# motor-slaves.net
KiCad netlist of a schematic drawn in EAGLE
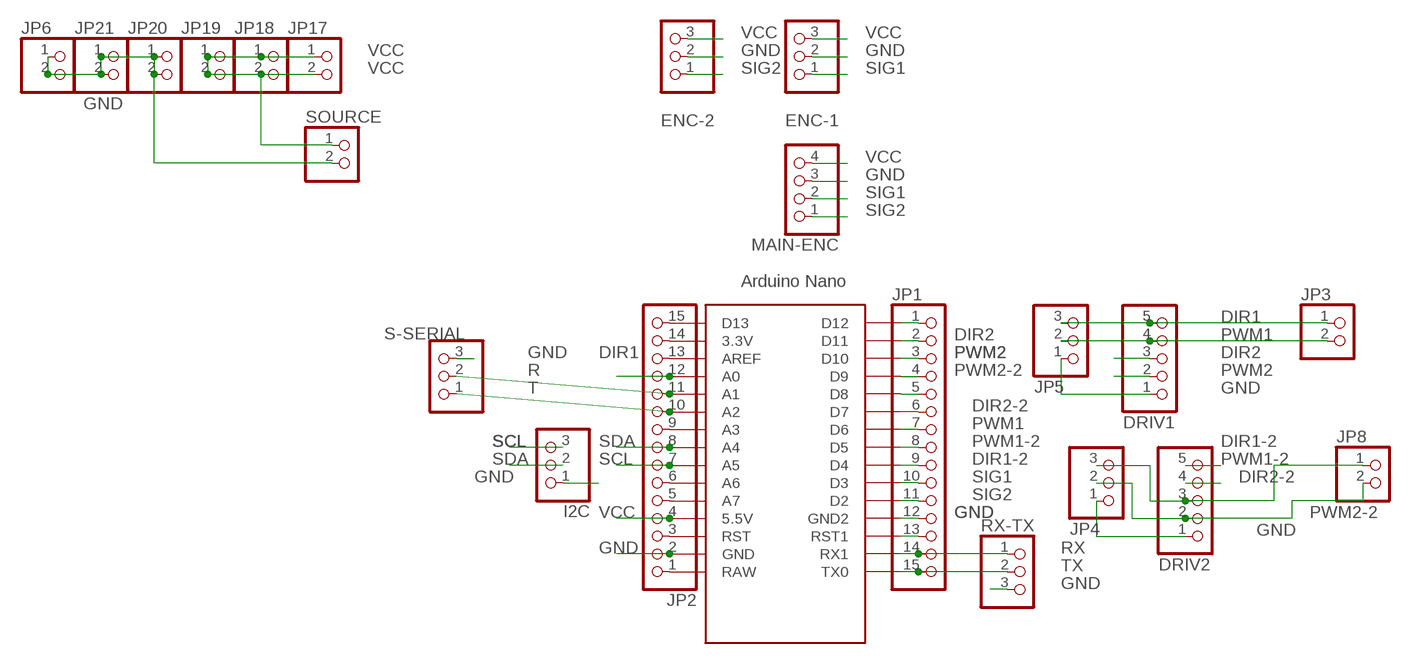
[diagram p0: schematic, sheet 1]

(export (version "E")
  (design (tool "Eeschema 10.0.6"))
  (components
    (comp (ref "DRIV1")
      (value "PINHD-5_DATA")
      (footprint "eagle-import:1X05_DATA")
      (libsource (lib "eagle-import") (part "PINHD-5_DATA"))
    )
    (comp (ref "DRIV2")
      (value "PINHD-5_DATA")
      (footprint "eagle-import:1X05_DATA")
      (libsource (lib "eagle-import") (part "PINHD-5_DATA"))
    )
    (comp (ref "ENC-1")
      (value "PINHD-3_DATA")
      (footprint "eagle-import:1X03_DATA")
      (libsource (lib "eagle-import") (part "PINHD-3_DATA"))
    )
    (comp (ref "ENC-2")
      (value "PINHD-3_DATA")
      (footprint "eagle-import:1X03_DATA")
      (libsource (lib "eagle-import") (part "PINHD-3_DATA"))
    )
    (comp (ref "I2C")
      (value "PINHD-3_DATA")
      (footprint "eagle-import:1X03_DATA")
      (libsource (lib "eagle-import") (part "PINHD-3_DATA"))
    )
    (comp (ref "JP1")
      (value "PINHD-1X15")
      (footprint "eagle-import:1X15")
      (libsource (lib "eagle-import") (part "PINHD-1X15"))
    )
    (comp (ref "JP2")
      (value "PINHD-1X15")
      (footprint "eagle-import:1X15")
      (libsource (lib "eagle-import") (part "PINHD-1X15"))
    )
    (comp (ref "JP3")
      (value "PINHD-2_DATA")
      (footprint "eagle-import:1X02_DATA")
      (libsource (lib "eagle-import") (part "PINHD-2_DATA"))
    )
    (comp (ref "JP4")
      (value "PINHD-3_DATA")
      (footprint "eagle-import:1X03_DATA")
      (libsource (lib "eagle-import") (part "PINHD-3_DATA"))
    )
    (comp (ref "JP5")
      (value "PINHD-3_DATA")
      (footprint "eagle-import:1X03_DATA")
      (libsource (lib "eagle-import") (part "PINHD-3_DATA"))
    )
    (comp (ref "JP6")
      (value "PINHD-1X2")
      (footprint "eagle-import:1X02")
      (libsource (lib "eagle-import") (part "PINHD-1X2"))
    )
    (comp (ref "JP8")
      (value "PINHD-2_DATA")
      (footprint "eagle-import:1X02_DATA")
      (libsource (lib "eagle-import") (part "PINHD-2_DATA"))
    )
    (comp (ref "JP17")
      (value "PINHD-1X2")
      (footprint "eagle-import:1X02")
      (libsource (lib "eagle-import") (part "PINHD-1X2"))
    )
    (comp (ref "JP18")
      (value "PINHD-1X2")
      (footprint "eagle-import:1X02")
      (libsource (lib "eagle-import") (part "PINHD-1X2"))
    )
    (comp (ref "JP19")
      (value "PINHD-1X2")
      (footprint "eagle-import:1X02")
      (libsource (lib "eagle-import") (part "PINHD-1X2"))
    )
    (comp (ref "JP20")
      (value "PINHD-1X2")
      (footprint "eagle-import:1X02")
      (libsource (lib "eagle-import") (part "PINHD-1X2"))
    )
    (comp (ref "JP21")
      (value "PINHD-1X2")
      (footprint "eagle-import:1X02")
      (libsource (lib "eagle-import") (part "PINHD-1X2"))
    )
    (comp (ref "MAIN-ENC")
      (value "PINHD-4_DATA")
      (footprint "eagle-import:1X04_DATA")
      (libsource (lib "eagle-import") (part "PINHD-4_DATA"))
    )
    (comp (ref "RX-TX")
      (value "PINHD-3_DATA")
      (footprint "eagle-import:1X03_DATA")
      (libsource (lib "eagle-import") (part "PINHD-3_DATA"))
    )
    (comp (ref "S-SERIAL")
      (value "PINHD-3_DATA")
      (footprint "eagle-import:1X03_DATA")
      (libsource (lib "eagle-import") (part "PINHD-3_DATA"))
    )
    (comp (ref "SOURCE")
      (value "PINHD-1X2")
      (footprint "eagle-import:1X02")
      (libsource (lib "eagle-import") (part "PINHD-1X2"))
    )
    (comp (ref "U$1")
      (value "ARDUINO_NANO")
      (footprint "eagle-import:NANO")
      (libsource (lib "eagle-import") (part "ARDUINO_NANO"))
    )
  )
  (nets
    (net (code "1") (name "/DIR1") (class "Default")
      (node (ref "DRIV1") (pin "5") (pinfunction "5_5") (pintype "passive"))
      (node (ref "JP2") (pin "12") (pinfunction "12_12") (pintype "passive"))
      (node (ref "JP3") (pin "1") (pinfunction "1_1") (pintype "passive"))
      (node (ref "JP5") (pin "3") (pinfunction "3_3") (pintype "passive"))
      (node (ref "U$1") (pin "A0") (pinfunction "A0_A0") (pintype "bidirectional"))
    )
    (net (code "2") (name "/DIR1-2") (class "Default")
      (node (ref "DRIV2") (pin "5") (pinfunction "5_5") (pintype "passive"))
      (node (ref "JP1") (pin "9") (pinfunction "9_9") (pintype "passive"))
      (node (ref "U$1") (pin "D4") (pinfunction "D4_D4") (pintype "bidirectional"))
    )
    (net (code "3") (name "/DIR2") (class "Default")
      (node (ref "DRIV1") (pin "3") (pinfunction "3_3") (pintype "passive"))
      (node (ref "JP1") (pin "2") (pinfunction "2_2") (pintype "passive"))
      (node (ref "U$1") (pin "D11") (pinfunction "D11_D11") (pintype "bidirectional"))
    )
    (net (code "4") (name "/DIR2-2") (class "Default")
      (node (ref "DRIV2") (pin "3") (pinfunction "3_3") (pintype "passive"))
      (node (ref "JP1") (pin "6") (pinfunction "6_6") (pintype "passive"))
      (node (ref "JP4") (pin "3") (pinfunction "3_3") (pintype "passive"))
      (node (ref "JP8") (pin "1") (pinfunction "1_1") (pintype "passive"))
      (node (ref "U$1") (pin "D7") (pinfunction "D7_D7") (pintype "bidirectional"))
    )
    (net (code "5") (name "/GND") (class "Default")
      (node (ref "DRIV1") (pin "1") (pinfunction "1_1") (pintype "passive"))
      (node (ref "DRIV2") (pin "1") (pinfunction "1_1") (pintype "passive"))
      (node (ref "ENC-1") (pin "2") (pinfunction "2_2") (pintype "passive"))
      (node (ref "ENC-2") (pin "2") (pinfunction "2_2") (pintype "passive"))
      (node (ref "I2C") (pin "1") (pinfunction "1_1") (pintype "passive"))
      (node (ref "JP1") (pin "12") (pinfunction "12_12") (pintype "passive"))
      (node (ref "JP2") (pin "2") (pinfunction "2_2") (pintype "passive"))
      (node (ref "JP20") (pin "1") (pinfunction "1_1") (pintype "passive"))
      (node (ref "JP20") (pin "2") (pinfunction "2_2") (pintype "passive"))
      (node (ref "JP21") (pin "1") (pinfunction "1_1") (pintype "passive"))
      (node (ref "JP21") (pin "2") (pinfunction "2_2") (pintype "passive"))
      (node (ref "JP4") (pin "1") (pinfunction "1_1") (pintype "passive"))
      (node (ref "JP5") (pin "1") (pinfunction "1_1") (pintype "passive"))
      (node (ref "JP6") (pin "1") (pinfunction "1_1") (pintype "passive"))
      (node (ref "JP6") (pin "2") (pinfunction "2_2") (pintype "passive"))
      (node (ref "MAIN-ENC") (pin "3") (pinfunction "3_3") (pintype "passive"))
      (node (ref "RX-TX") (pin "3") (pinfunction "3_3") (pintype "passive"))
      (node (ref "S-SERIAL") (pin "3") (pinfunction "3_3") (pintype "passive"))
      (node (ref "SOURCE") (pin "2") (pinfunction "2_2") (pintype "passive"))
      (node (ref "U$1") (pin "GND") (pinfunction "GND_GND") (pintype "bidirectional"))
      (node (ref "U$1") (pin "GND1") (pinfunction "GND2_GND1") (pintype "bidirectional"))
    )
    (net (code "6") (name "/PWM1") (class "Default")
      (node (ref "DRIV1") (pin "4") (pinfunction "4_4") (pintype "passive"))
      (node (ref "JP1") (pin "7") (pinfunction "7_7") (pintype "passive"))
      (node (ref "JP3") (pin "2") (pinfunction "2_2") (pintype "passive"))
      (node (ref "JP5") (pin "2") (pinfunction "2_2") (pintype "passive"))
      (node (ref "U$1") (pin "D6") (pinfunction "D6_D6") (pintype "bidirectional"))
    )
    (net (code "7") (name "/PWM1-2") (class "Default")
      (node (ref "DRIV2") (pin "4") (pinfunction "4_4") (pintype "passive"))
      (node (ref "JP1") (pin "8") (pinfunction "8_8") (pintype "passive"))
      (node (ref "U$1") (pin "D5") (pinfunction "D5_D5") (pintype "bidirectional"))
    )
    (net (code "8") (name "/PWM2") (class "Default")
      (node (ref "DRIV1") (pin "2") (pinfunction "2_2") (pintype "passive"))
      (node (ref "JP1") (pin "3") (pinfunction "3_3") (pintype "passive"))
      (node (ref "U$1") (pin "D10") (pinfunction "D10_D10") (pintype "bidirectional"))
    )
    (net (code "9") (name "/PWM2-2") (class "Default")
      (node (ref "DRIV2") (pin "2") (pinfunction "2_2") (pintype "passive"))
      (node (ref "JP1") (pin "4") (pinfunction "4_4") (pintype "passive"))
      (node (ref "JP4") (pin "2") (pinfunction "2_2") (pintype "passive"))
      (node (ref "JP8") (pin "2") (pinfunction "2_2") (pintype "passive"))
      (node (ref "U$1") (pin "D9") (pinfunction "D9_D9") (pintype "bidirectional"))
    )
    (net (code "10") (name "/R") (class "Default")
      (node (ref "JP2") (pin "11") (pinfunction "11_11") (pintype "passive"))
      (node (ref "S-SERIAL") (pin "2") (pinfunction "2_2") (pintype "passive"))
      (node (ref "U$1") (pin "A1") (pinfunction "A1_A1") (pintype "bidirectional"))
    )
    (net (code "11") (name "/RX") (class "Default")
      (node (ref "JP1") (pin "14") (pinfunction "14_14") (pintype "passive"))
      (node (ref "RX-TX") (pin "1") (pinfunction "1_1") (pintype "passive"))
      (node (ref "U$1") (pin "RX1") (pinfunction "RX1_RX1") (pintype "bidirectional"))
    )
    (net (code "12") (name "/SCL") (class "Default")
      (node (ref "I2C") (pin "3") (pinfunction "3_3") (pintype "passive"))
      (node (ref "JP2") (pin "7") (pinfunction "7_7") (pintype "passive"))
      (node (ref "U$1") (pin "A5") (pinfunction "A5_A5") (pintype "bidirectional"))
    )
    (net (code "13") (name "/SDA") (class "Default")
      (node (ref "I2C") (pin "2") (pinfunction "2_2") (pintype "passive"))
      (node (ref "JP2") (pin "8") (pinfunction "8_8") (pintype "passive"))
      (node (ref "U$1") (pin "A4") (pinfunction "A4_A4") (pintype "bidirectional"))
    )
    (net (code "14") (name "/SIG1") (class "Default")
      (node (ref "ENC-1") (pin "1") (pinfunction "1_1") (pintype "passive"))
      (node (ref "JP1") (pin "10") (pinfunction "10_10") (pintype "passive"))
      (node (ref "MAIN-ENC") (pin "2") (pinfunction "2_2") (pintype "passive"))
      (node (ref "U$1") (pin "D3") (pinfunction "D3_D3") (pintype "bidirectional"))
    )
    (net (code "15") (name "/SIG2") (class "Default")
      (node (ref "ENC-2") (pin "1") (pinfunction "1_1") (pintype "passive"))
      (node (ref "JP1") (pin "11") (pinfunction "11_11") (pintype "passive"))
      (node (ref "MAIN-ENC") (pin "1") (pinfunction "1_1") (pintype "passive"))
      (node (ref "U$1") (pin "D2") (pinfunction "D2_D2") (pintype "bidirectional"))
    )
    (net (code "16") (name "/T") (class "Default")
      (node (ref "JP2") (pin "10") (pinfunction "10_10") (pintype "passive"))
      (node (ref "S-SERIAL") (pin "1") (pinfunction "1_1") (pintype "passive"))
      (node (ref "U$1") (pin "A2") (pinfunction "A2_A2") (pintype "bidirectional"))
    )
    (net (code "17") (name "/TX") (class "Default")
      (node (ref "JP1") (pin "15") (pinfunction "15_15") (pintype "passive"))
      (node (ref "RX-TX") (pin "2") (pinfunction "2_2") (pintype "passive"))
      (node (ref "U$1") (pin "TX0") (pinfunction "TX0_TX0") (pintype "bidirectional"))
    )
    (net (code "18") (name "/VCC") (class "Default")
      (node (ref "ENC-1") (pin "3") (pinfunction "3_3") (pintype "passive"))
      (node (ref "ENC-2") (pin "3") (pinfunction "3_3") (pintype "passive"))
      (node (ref "JP17") (pin "1") (pinfunction "1_1") (pintype "passive"))
      (node (ref "JP17") (pin "2") (pinfunction "2_2") (pintype "passive"))
      (node (ref "JP18") (pin "1") (pinfunction "1_1") (pintype "passive"))
      (node (ref "JP18") (pin "2") (pinfunction "2_2") (pintype "passive"))
      (node (ref "JP19") (pin "1") (pinfunction "1_1") (pintype "passive"))
      (node (ref "JP19") (pin "2") (pinfunction "2_2") (pintype "passive"))
      (node (ref "JP2") (pin "4") (pinfunction "4_4") (pintype "passive"))
      (node (ref "MAIN-ENC") (pin "4") (pinfunction "4_4") (pintype "passive"))
      (node (ref "SOURCE") (pin "1") (pinfunction "1_1") (pintype "passive"))
      (node (ref "U$1") (pin "5V") (pinfunction "5.5V_5V") (pintype "bidirectional"))
    )
    (net (code "19") (name "Net-(JP1-Pad1)") (class "Default")
      (node (ref "JP1") (pin "1") (pinfunction "1_1") (pintype "passive"))
      (node (ref "U$1") (pin "D12") (pinfunction "D12_D12") (pintype "bidirectional"))
    )
    (net (code "20") (name "Net-(JP1-Pad5)") (class "Default")
      (node (ref "JP1") (pin "5") (pinfunction "5_5") (pintype "passive"))
      (node (ref "U$1") (pin "D8") (pinfunction "D8_D8") (pintype "bidirectional"))
    )
    (net (code "21") (name "Net-(JP1-Pad13)") (class "Default")
      (node (ref "JP1") (pin "13") (pinfunction "13_13") (pintype "passive"))
      (node (ref "U$1") (pin "RST1") (pinfunction "RST1_RST1") (pintype "bidirectional"))
    )
    (net (code "22") (name "Net-(JP2-Pad1)") (class "Default")
      (node (ref "JP2") (pin "1") (pinfunction "1_1") (pintype "passive"))
      (node (ref "U$1") (pin "RAW") (pinfunction "RAW_RAW") (pintype "bidirectional"))
    )
    (net (code "23") (name "Net-(JP2-Pad3)") (class "Default")
      (node (ref "JP2") (pin "3") (pinfunction "3_3") (pintype "passive"))
      (node (ref "U$1") (pin "RST") (pinfunction "RST_RST") (pintype "bidirectional"))
    )
    (net (code "24") (name "Net-(JP2-Pad5)") (class "Default")
      (node (ref "JP2") (pin "5") (pinfunction "5_5") (pintype "passive"))
      (node (ref "U$1") (pin "A7") (pinfunction "A7_A7") (pintype "bidirectional"))
    )
    (net (code "25") (name "Net-(JP2-Pad6)") (class "Default")
      (node (ref "JP2") (pin "6") (pinfunction "6_6") (pintype "passive"))
      (node (ref "U$1") (pin "A6") (pinfunction "A6_A6") (pintype "bidirectional"))
    )
    (net (code "26") (name "Net-(JP2-Pad9)") (class "Default")
      (node (ref "JP2") (pin "9") (pinfunction "9_9") (pintype "passive"))
      (node (ref "U$1") (pin "A3") (pinfunction "A3_A3") (pintype "bidirectional"))
    )
    (net (code "27") (name "Net-(JP2-Pad13)") (class "Default")
      (node (ref "JP2") (pin "13") (pinfunction "13_13") (pintype "passive"))
      (node (ref "U$1") (pin "AREF") (pinfunction "AREF_AREF") (pintype "bidirectional"))
    )
    (net (code "28") (name "Net-(JP2-Pad14)") (class "Default")
      (node (ref "JP2") (pin "14") (pinfunction "14_14") (pintype "passive"))
      (node (ref "U$1") (pin "3.3V") (pinfunction "3.3V_3.3V") (pintype "bidirectional"))
    )
    (net (code "29") (name "Net-(JP2-Pad15)") (class "Default")
      (node (ref "JP2") (pin "15") (pinfunction "15_15") (pintype "passive"))
      (node (ref "U$1") (pin "D13") (pinfunction "D13_D13") (pintype "bidirectional"))
    )
  )
)
